# Menu_Navigators.net
KiCad netlist of a schematic drawn in Altium Designer
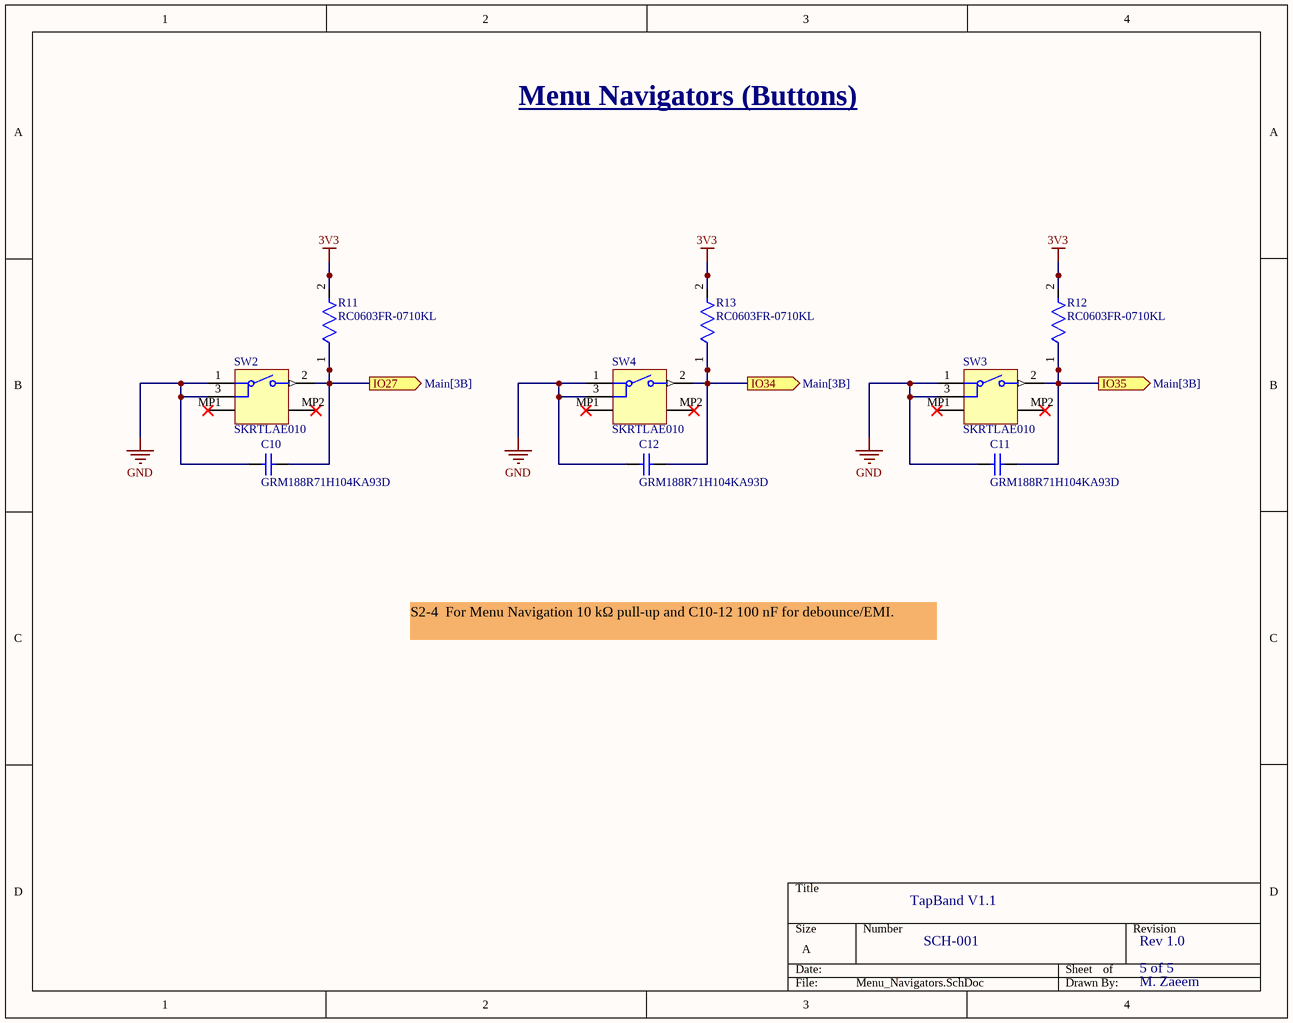
[diagram p0: Menu_Navigators.SchDoc]

(export (version "E")
  (design (tool "Eeschema 10.0.6"))
  (components
    (comp (ref "C10")
      (value "GRM188R71H104KA93D")
      (footprint "CAPC1608X90X35ML10T15")
      (description "Chip Capacitor, 0.1 uF, +/- 10%, 50 V, -55 to 125 degC, 0603 (1608 Metric), RoHS, Tape and Reel")
      (fields (field (name "TOLERANCE") "10%") (field (name "VOLTAGE") "50V"))
      (libsource (lib "Altium Content Vault") (part "CAP-NP-2"))
    )
    (comp (ref "C11")
      (value "GRM188R71H104KA93D")
      (footprint "CAPC1608X90X35ML10T15")
      (description "Chip Capacitor, 0.1 uF, +/- 10%, 50 V, -55 to 125 degC, 0603 (1608 Metric), RoHS, Tape and Reel")
      (fields (field (name "TOLERANCE") "10%") (field (name "VOLTAGE") "50V"))
      (libsource (lib "Altium Content Vault") (part "CAP-NP-2"))
    )
    (comp (ref "C12")
      (value "GRM188R71H104KA93D")
      (footprint "CAPC1608X90X35ML10T15")
      (description "Chip Capacitor, 0.1 uF, +/- 10%, 50 V, -55 to 125 degC, 0603 (1608 Metric), RoHS, Tape and Reel")
      (fields (field (name "TOLERANCE") "10%") (field (name "VOLTAGE") "50V"))
      (libsource (lib "Altium Content Vault") (part "CAP-NP-2"))
    )
    (comp (ref "R11")
      (value "RC0603FR-0710KL")
      (footprint "FP-RC0603-0_55-IPC_C")
      (description "RES 10K OHM 1% 1/10W 0603")
      (fields (field (name "TOLERANCE") "1%"))
      (libsource (lib "Altium Content Vault") (part "1029c3af85768c4190bb7ad29bc67b5"))
    )
    (comp (ref "R12")
      (value "RC0603FR-0710KL")
      (footprint "FP-RC0603-0_55-IPC_C")
      (description "RES 10K OHM 1% 1/10W 0603")
      (fields (field (name "TOLERANCE") "1%"))
      (libsource (lib "Altium Content Vault") (part "1029c3af85768c4190bb7ad29bc67b5"))
    )
    (comp (ref "R13")
      (value "RC0603FR-0710KL")
      (footprint "FP-RC0603-0_55-IPC_C")
      (description "RES 10K OHM 1% 1/10W 0603")
      (fields (field (name "TOLERANCE") "1%"))
      (libsource (lib "Altium Content Vault") (part "1029c3af85768c4190bb7ad29bc67b5"))
    )
    (comp (ref "SW2")
      (value "SKRTLAE010")
      (footprint "ALPS-SKRTLAE010_V")
      (description "Side Push Type, 250 V, -40 to 90 degC, 3-Pin SMD, RoHS, Tape and Reel")
      (fields (field (name "MANUFACTURER") "ALPS"))
      (libsource (lib "Altium Content Vault") (part "SW_SPST-3_A"))
    )
    (comp (ref "SW3")
      (value "SKRTLAE010")
      (footprint "ALPS-SKRTLAE010_V")
      (description "Side Push Type, 250 V, -40 to 90 degC, 3-Pin SMD, RoHS, Tape and Reel")
      (fields (field (name "MANUFACTURER") "ALPS"))
      (libsource (lib "Altium Content Vault") (part "SW_SPST-3_A"))
    )
    (comp (ref "SW4")
      (value "SKRTLAE010")
      (footprint "ALPS-SKRTLAE010_V")
      (description "Side Push Type, 250 V, -40 to 90 degC, 3-Pin SMD, RoHS, Tape and Reel")
      (fields (field (name "MANUFACTURER") "ALPS"))
      (libsource (lib "Altium Content Vault") (part "SW_SPST-3_A"))
    )
  )
  (nets
    (net (code "1") (name "/IO27") (class "Default")
      (node (ref "C10") (pin "1") (pinfunction "1_1") (pintype "passive"))
      (node (ref "R11") (pin "1") (pinfunction "1_1") (pintype "passive"))
      (node (ref "SW2") (pin "2") (pinfunction "2_2") (pintype "output"))
    )
    (net (code "2") (name "/IO34") (class "Default")
      (node (ref "C12") (pin "1") (pinfunction "1_1") (pintype "passive"))
      (node (ref "R13") (pin "1") (pinfunction "1_1") (pintype "passive"))
      (node (ref "SW4") (pin "2") (pinfunction "2_2") (pintype "output"))
    )
    (net (code "3") (name "/IO35") (class "Default")
      (node (ref "C11") (pin "1") (pinfunction "1_1") (pintype "passive"))
      (node (ref "R12") (pin "1") (pinfunction "1_1") (pintype "passive"))
      (node (ref "SW3") (pin "2") (pinfunction "2_2") (pintype "output"))
    )
    (net (code "4") (name "3V3") (class "Default")
      (node (ref "R11") (pin "2") (pinfunction "2_2") (pintype "passive"))
      (node (ref "R12") (pin "2") (pinfunction "2_2") (pintype "passive"))
      (node (ref "R13") (pin "2") (pinfunction "2_2") (pintype "passive"))
    )
    (net (code "5") (name "GND") (class "Default")
      (node (ref "C10") (pin "2") (pinfunction "2_2") (pintype "passive"))
      (node (ref "C11") (pin "2") (pinfunction "2_2") (pintype "passive"))
      (node (ref "C12") (pin "2") (pinfunction "2_2") (pintype "passive"))
      (node (ref "SW2") (pin "1") (pinfunction "1_1") (pintype "passive"))
      (node (ref "SW2") (pin "3") (pinfunction "3_3") (pintype "passive"))
      (node (ref "SW3") (pin "1") (pinfunction "1_1") (pintype "passive"))
      (node (ref "SW3") (pin "3") (pinfunction "3_3") (pintype "passive"))
      (node (ref "SW4") (pin "1") (pinfunction "1_1") (pintype "passive"))
      (node (ref "SW4") (pin "3") (pinfunction "3_3") (pintype "passive"))
    )
    (net (code "6") (name "unconnected-(SW2-PadMP1)") (class "Default")
      (node (ref "SW2") (pin "MP1") (pinfunction "MP1_MP1") (pintype "passive+no_connect"))
    )
    (net (code "7") (name "unconnected-(SW2-PadMP2)") (class "Default")
      (node (ref "SW2") (pin "MP2") (pinfunction "MP2_MP2") (pintype "passive+no_connect"))
    )
    (net (code "8") (name "unconnected-(SW3-PadMP1)") (class "Default")
      (node (ref "SW3") (pin "MP1") (pinfunction "MP1_MP1") (pintype "passive+no_connect"))
    )
    (net (code "9") (name "unconnected-(SW3-PadMP2)") (class "Default")
      (node (ref "SW3") (pin "MP2") (pinfunction "MP2_MP2") (pintype "passive+no_connect"))
    )
    (net (code "10") (name "unconnected-(SW4-PadMP1)") (class "Default")
      (node (ref "SW4") (pin "MP1") (pinfunction "MP1_MP1") (pintype "passive+no_connect"))
    )
    (net (code "11") (name "unconnected-(SW4-PadMP2)") (class "Default")
      (node (ref "SW4") (pin "MP2") (pinfunction "MP2_MP2") (pintype "passive+no_connect"))
    )
  )
)
